# PowerSound9x_v002.net
KiCad netlist of a schematic drawn in EAGLE
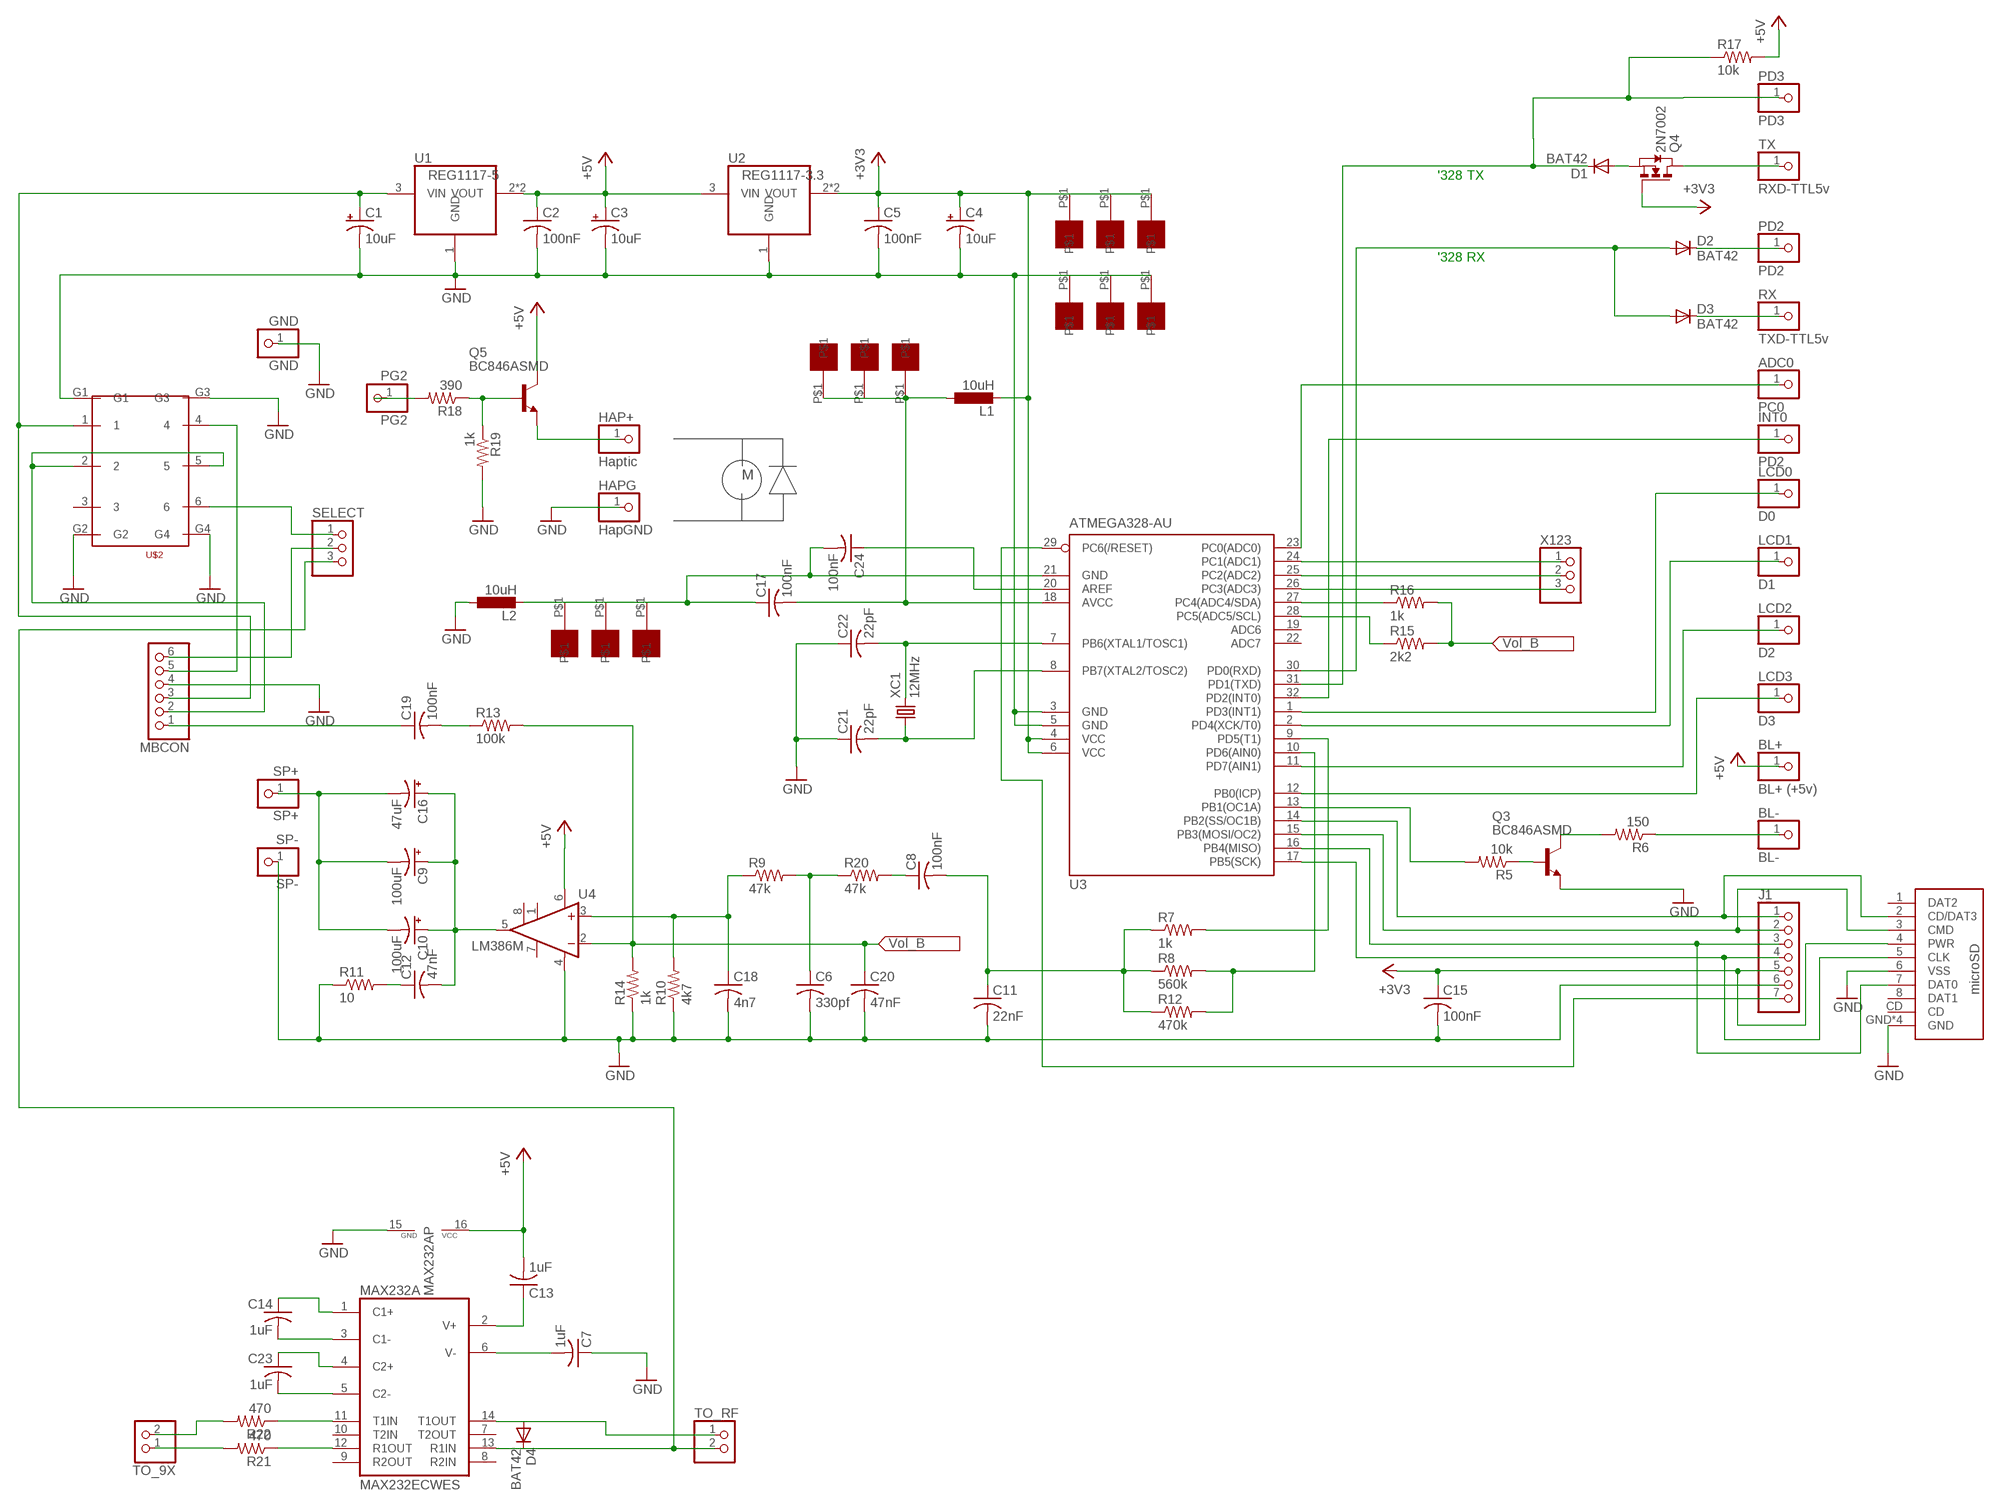
[diagram p0: schematic, sheet 1]

(export (version "E")
  (design (tool "Eeschema 10.0.6"))
  (components
    (comp (ref "ADC0")
      (value "PC0")
      (footprint "eagle-import:1X01")
      (libsource (lib "eagle-import") (part "PINHD-1X1"))
    )
    (comp (ref "BL+")
      (value "BL+ (+5v)")
      (footprint "eagle-import:1X01")
      (libsource (lib "eagle-import") (part "PINHD-1X1"))
    )
    (comp (ref "BL-")
      (value "BL-")
      (footprint "eagle-import:1X01")
      (libsource (lib "eagle-import") (part "PINHD-1X1"))
    )
    (comp (ref "C1")
      (value "10uF")
      (footprint "eagle-import:CT3528")
      (libsource (lib "eagle-import") (part "CPOL-USCT3528"))
    )
    (comp (ref "C2")
      (value "100nF")
      (footprint "eagle-import:C1206")
      (libsource (lib "eagle-import") (part "C-USC1206"))
    )
    (comp (ref "C3")
      (value "10uF")
      (footprint "eagle-import:CT3528")
      (libsource (lib "eagle-import") (part "CPOL-USCT3528"))
    )
    (comp (ref "C4")
      (value "10uF")
      (footprint "eagle-import:CT3528")
      (libsource (lib "eagle-import") (part "CPOL-USCT3528"))
    )
    (comp (ref "C5")
      (value "100nF")
      (footprint "eagle-import:C1206")
      (libsource (lib "eagle-import") (part "C-USC1206"))
    )
    (comp (ref "C6")
      (value "330pf")
      (footprint "eagle-import:C1206")
      (libsource (lib "eagle-import") (part "C-USC1206"))
    )
    (comp (ref "C7")
      (value "1uF")
      (footprint "eagle-import:C1206")
      (libsource (lib "eagle-import") (part "C-USC1206"))
    )
    (comp (ref "C8")
      (value "100nF")
      (footprint "eagle-import:C1206")
      (libsource (lib "eagle-import") (part "C-USC1206"))
    )
    (comp (ref "C9")
      (value "100uF")
      (footprint "eagle-import:CT6032")
      (libsource (lib "eagle-import") (part "CPOL-USCT6032"))
    )
    (comp (ref "C10")
      (value "100uF")
      (footprint "eagle-import:CT6032")
      (libsource (lib "eagle-import") (part "CPOL-USCT6032"))
    )
    (comp (ref "C11")
      (value "22nF")
      (footprint "eagle-import:C1206")
      (libsource (lib "eagle-import") (part "C-USC1206"))
    )
    (comp (ref "C12")
      (value "47nF")
      (footprint "eagle-import:C1206")
      (libsource (lib "eagle-import") (part "C-USC1206"))
    )
    (comp (ref "C13")
      (value "1uF")
      (footprint "eagle-import:C1206")
      (libsource (lib "eagle-import") (part "C-USC1206"))
    )
    (comp (ref "C14")
      (value "1uF")
      (footprint "eagle-import:C1206")
      (libsource (lib "eagle-import") (part "C-USC1206"))
    )
    (comp (ref "C15")
      (value "100nF")
      (footprint "eagle-import:C1206")
      (libsource (lib "eagle-import") (part "C-USC1206"))
    )
    (comp (ref "C16")
      (value "47uF")
      (footprint "eagle-import:CT6032")
      (libsource (lib "eagle-import") (part "CPOL-USCT6032"))
    )
    (comp (ref "C17")
      (value "100nF")
      (footprint "eagle-import:C1206")
      (libsource (lib "eagle-import") (part "C-USC1206"))
    )
    (comp (ref "C18")
      (value "4n7")
      (footprint "eagle-import:C1206")
      (libsource (lib "eagle-import") (part "C-USC1206"))
    )
    (comp (ref "C19")
      (value "100nF")
      (footprint "eagle-import:C1206")
      (libsource (lib "eagle-import") (part "C-USC1206"))
    )
    (comp (ref "C20")
      (value "47nF")
      (footprint "eagle-import:C1206")
      (libsource (lib "eagle-import") (part "C-USC1206"))
    )
    (comp (ref "C21")
      (value "22pF")
      (footprint "eagle-import:C1206")
      (libsource (lib "eagle-import") (part "C-USC1206"))
    )
    (comp (ref "C22")
      (value "22pF")
      (footprint "eagle-import:C1206")
      (libsource (lib "eagle-import") (part "C-USC1206"))
    )
    (comp (ref "C23")
      (value "1uF")
      (footprint "eagle-import:C1206")
      (libsource (lib "eagle-import") (part "C-USC1206"))
    )
    (comp (ref "C24")
      (value "100nF")
      (footprint "eagle-import:C1206")
      (libsource (lib "eagle-import") (part "C-USC1206"))
    )
    (comp (ref "D1")
      (value "BAT42")
      (footprint "eagle-import:SOD123")
      (libsource (lib "eagle-import") (part "DIODE-SOD123"))
    )
    (comp (ref "D2")
      (value "BAT42")
      (footprint "eagle-import:SOD123")
      (libsource (lib "eagle-import") (part "DIODE-SOD123"))
    )
    (comp (ref "D3")
      (value "BAT42")
      (footprint "eagle-import:SOD123")
      (libsource (lib "eagle-import") (part "DIODE-SOD123"))
    )
    (comp (ref "D4")
      (value "BAT42")
      (footprint "eagle-import:SOD123")
      (libsource (lib "eagle-import") (part "DIODE-SOD123"))
    )
    (comp (ref "GND")
      (value "GND")
      (footprint "eagle-import:1X01")
      (libsource (lib "eagle-import") (part "PINHD-1X1"))
    )
    (comp (ref "HAP+")
      (value "Haptic")
      (footprint "eagle-import:1X01")
      (libsource (lib "eagle-import") (part "PINHD-1X1"))
    )
    (comp (ref "HAPG")
      (value "HapGND")
      (footprint "eagle-import:1X01")
      (libsource (lib "eagle-import") (part "PINHD-1X1"))
    )
    (comp (ref "INT0")
      (value "PD2")
      (footprint "eagle-import:1X01")
      (libsource (lib "eagle-import") (part "PINHD-1X1"))
    )
    (comp (ref "J1")
      (value "PINHD-1X7")
      (footprint "eagle-import:1X07")
      (libsource (lib "eagle-import") (part "PINHD-1X7"))
    )
    (comp (ref "L1")
      (value "10uH")
      (footprint "eagle-import:L3225M")
      (libsource (lib "eagle-import") (part "L-EUL3225M"))
    )
    (comp (ref "L2")
      (value "10uH")
      (footprint "eagle-import:L3225M")
      (libsource (lib "eagle-import") (part "L-EUL3225M"))
    )
    (comp (ref "LCD0")
      (value "D0")
      (footprint "eagle-import:1X01")
      (libsource (lib "eagle-import") (part "PINHD-1X1"))
    )
    (comp (ref "LCD1")
      (value "D1")
      (footprint "eagle-import:1X01")
      (libsource (lib "eagle-import") (part "PINHD-1X1"))
    )
    (comp (ref "LCD2")
      (value "D2")
      (footprint "eagle-import:1X01")
      (libsource (lib "eagle-import") (part "PINHD-1X1"))
    )
    (comp (ref "LCD3")
      (value "D3")
      (footprint "eagle-import:1X01")
      (libsource (lib "eagle-import") (part "PINHD-1X1"))
    )
    (comp (ref "MAX232A")
      (value "MAX232ECWES")
      (footprint "eagle-import:SO16")
      (libsource (lib "eagle-import") (part "MAX232ECWES"))
    )
    (comp (ref "MBCON")
      (value "PINHD-1X6")
      (footprint "eagle-import:1X06")
      (libsource (lib "eagle-import") (part "PINHD-1X6"))
    )
    (comp (ref "PD2")
      (value "PD2")
      (footprint "eagle-import:1X01")
      (libsource (lib "eagle-import") (part "PINHD-1X1"))
    )
    (comp (ref "PD3")
      (value "PD3")
      (footprint "eagle-import:1X01")
      (libsource (lib "eagle-import") (part "PINHD-1X1"))
    )
    (comp (ref "PG2")
      (value "PG2")
      (footprint "eagle-import:1X01")
      (libsource (lib "eagle-import") (part "PINHD-1X1"))
    )
    (comp (ref "Q3")
      (value "BC846ASMD")
      (footprint "eagle-import:SOT23")
      (libsource (lib "eagle-import") (part "BC846SMDA"))
    )
    (comp (ref "Q4")
      (value "2N7002")
      (footprint "eagle-import:SOT-23")
      (libsource (lib "eagle-import") (part "NMOSSOT23"))
    )
    (comp (ref "Q5")
      (value "BC846ASMD")
      (footprint "eagle-import:SOT23")
      (libsource (lib "eagle-import") (part "BC846SMDA"))
    )
    (comp (ref "R5")
      (value "10k")
      (footprint "eagle-import:R1206")
      (libsource (lib "eagle-import") (part "R-US_R1206"))
    )
    (comp (ref "R6")
      (value "150")
      (footprint "eagle-import:R1206")
      (libsource (lib "eagle-import") (part "R-US_R1206"))
    )
    (comp (ref "R7")
      (value "1k")
      (footprint "eagle-import:R1206")
      (libsource (lib "eagle-import") (part "R-US_R1206"))
    )
    (comp (ref "R8")
      (value "560k")
      (footprint "eagle-import:R1206")
      (libsource (lib "eagle-import") (part "R-US_R1206"))
    )
    (comp (ref "R9")
      (value "47k")
      (footprint "eagle-import:R1206")
      (libsource (lib "eagle-import") (part "R-US_R1206"))
    )
    (comp (ref "R10")
      (value "4k7")
      (footprint "eagle-import:R1206")
      (libsource (lib "eagle-import") (part "R-US_R1206"))
    )
    (comp (ref "R11")
      (value "10")
      (footprint "eagle-import:R1206")
      (libsource (lib "eagle-import") (part "R-US_R1206"))
    )
    (comp (ref "R12")
      (value "470k")
      (footprint "eagle-import:R1206")
      (libsource (lib "eagle-import") (part "R-US_R1206"))
    )
    (comp (ref "R13")
      (value "100k")
      (footprint "eagle-import:R1206")
      (libsource (lib "eagle-import") (part "R-US_R1206"))
    )
    (comp (ref "R14")
      (value "1k")
      (footprint "eagle-import:R1206")
      (libsource (lib "eagle-import") (part "R-US_R1206"))
    )
    (comp (ref "R15")
      (value "2k2")
      (footprint "eagle-import:R1206")
      (libsource (lib "eagle-import") (part "R-US_R1206"))
    )
    (comp (ref "R16")
      (value "1k")
      (footprint "eagle-import:R1206")
      (libsource (lib "eagle-import") (part "R-US_R1206"))
    )
    (comp (ref "R17")
      (value "10k")
      (footprint "eagle-import:R1206")
      (libsource (lib "eagle-import") (part "R-US_R1206"))
    )
    (comp (ref "R18")
      (value "390")
      (footprint "eagle-import:R1206")
      (libsource (lib "eagle-import") (part "R-US_R1206"))
    )
    (comp (ref "R19")
      (value "1k")
      (footprint "eagle-import:R1206")
      (libsource (lib "eagle-import") (part "R-US_R1206"))
    )
    (comp (ref "R20")
      (value "47k")
      (footprint "eagle-import:R1206")
      (libsource (lib "eagle-import") (part "R-US_R1206"))
    )
    (comp (ref "R21")
      (value "470")
      (footprint "eagle-import:R1206")
      (libsource (lib "eagle-import") (part "R-US_R1206"))
    )
    (comp (ref "R22")
      (value "470")
      (footprint "eagle-import:R1206")
      (libsource (lib "eagle-import") (part "R-US_R1206"))
    )
    (comp (ref "RX")
      (value "TXD-TTL5v")
      (footprint "eagle-import:1X01")
      (libsource (lib "eagle-import") (part "PINHD-1X1"))
    )
    (comp (ref "SELECT")
      (value "PINHD-1X3")
      (footprint "eagle-import:1X03")
      (libsource (lib "eagle-import") (part "PINHD-1X3"))
    )
    (comp (ref "SP+")
      (value "SP+")
      (footprint "eagle-import:1X01")
      (libsource (lib "eagle-import") (part "PINHD-1X1"))
    )
    (comp (ref "SP-")
      (value "SP-")
      (footprint "eagle-import:1X01")
      (libsource (lib "eagle-import") (part "PINHD-1X1"))
    )
    (comp (ref "TO_9X")
      (value "PINHD-1X2")
      (footprint "eagle-import:1X02")
      (libsource (lib "eagle-import") (part "PINHD-1X2"))
    )
    (comp (ref "TO_RF")
      (value "PINHD-1X2")
      (footprint "eagle-import:1X02")
      (libsource (lib "eagle-import") (part "PINHD-1X2"))
    )
    (comp (ref "TX")
      (value "RXD-TTL5v")
      (footprint "eagle-import:1X01")
      (libsource (lib "eagle-import") (part "PINHD-1X1"))
    )
    (comp (ref "U$1")
      (value "PAD")
      (footprint "eagle-import:PAD")
      (libsource (lib "eagle-import") (part "PAD"))
    )
    (comp (ref "U$2")
      (value "SS22H02SS22H02")
      (footprint "eagle-import:SS22H02")
      (libsource (lib "eagle-import") (part "SS22H02SS22H02"))
    )
    (comp (ref "U$3")
      (value "112J-TDAR-R")
      (footprint "eagle-import:112J-TDAR-R")
      (libsource (lib "eagle-import") (part "112J-TDAR-R"))
    )
    (comp (ref "U$4")
      (value "PAD")
      (footprint "eagle-import:PAD")
      (libsource (lib "eagle-import") (part "PAD"))
    )
    (comp (ref "U$5")
      (value "PAD")
      (footprint "eagle-import:PAD")
      (libsource (lib "eagle-import") (part "PAD"))
    )
    (comp (ref "U$6")
      (value "PAD")
      (footprint "eagle-import:PAD")
      (libsource (lib "eagle-import") (part "PAD"))
    )
    (comp (ref "U$7")
      (value "PAD")
      (footprint "eagle-import:PAD")
      (libsource (lib "eagle-import") (part "PAD"))
    )
    (comp (ref "U$8")
      (value "PAD")
      (footprint "eagle-import:PAD")
      (libsource (lib "eagle-import") (part "PAD"))
    )
    (comp (ref "U$9")
      (value "PAD")
      (footprint "eagle-import:PAD")
      (libsource (lib "eagle-import") (part "PAD"))
    )
    (comp (ref "U$10")
      (value "PAD")
      (footprint "eagle-import:PAD")
      (libsource (lib "eagle-import") (part "PAD"))
    )
    (comp (ref "U$11")
      (value "PAD")
      (footprint "eagle-import:PAD")
      (libsource (lib "eagle-import") (part "PAD"))
    )
    (comp (ref "U$12")
      (value "PAD")
      (footprint "eagle-import:PAD")
      (libsource (lib "eagle-import") (part "PAD"))
    )
    (comp (ref "U$13")
      (value "PAD")
      (footprint "eagle-import:PAD")
      (libsource (lib "eagle-import") (part "PAD"))
    )
    (comp (ref "U$14")
      (value "PAD")
      (footprint "eagle-import:PAD")
      (libsource (lib "eagle-import") (part "PAD"))
    )
    (comp (ref "U1")
      (value "REG1117-5")
      (footprint "eagle-import:SOT223")
      (fields (field (name "MPN") "REG1117"))
      (libsource (lib "eagle-import") (part "REG1117"))
    )
    (comp (ref "U2")
      (value "REG1117-3.3")
      (footprint "eagle-import:SOT223")
      (fields (field (name "MPN") "REG1117"))
      (libsource (lib "eagle-import") (part "REG1117"))
    )
    (comp (ref "U3")
      (value "ATMEGA328-AU")
      (footprint "eagle-import:TQFP32-08")
      (fields (field (name "MPN") "ATMEGA8-16AU"))
      (libsource (lib "eagle-import") (part "MEGA8-AI"))
    )
    (comp (ref "U4")
      (value "LM386M")
      (footprint "eagle-import:SO08")
      (libsource (lib "eagle-import") (part "LM386?-M1"))
    )
    (comp (ref "X123")
      (value "PINHD-1X3")
      (footprint "eagle-import:1X03")
      (libsource (lib "eagle-import") (part "PINHD-1X3"))
    )
    (comp (ref "XC1")
      (value "12MHz")
      (footprint "eagle-import:HC49UP")
      (libsource (lib "eagle-import") (part "CRYSTALHC49UP"))
    )
  )
  (nets
    (net (code "1") (name "+3V3") (class "Default")
      (node (ref "C15") (pin "1") (pinfunction "1_1") (pintype "passive"))
      (node (ref "C4") (pin "+") (pinfunction "+_+") (pintype "passive"))
      (node (ref "C5") (pin "1") (pinfunction "1_1") (pintype "passive"))
      (node (ref "J1") (pin "5") (pinfunction "5_5") (pintype "passive"))
      (node (ref "L1") (pin "2") (pinfunction "2_2") (pintype "passive"))
      (node (ref "Q4") (pin "3") (pinfunction "G_3") (pintype "passive"))
      (node (ref "U$10") (pin "P$1") (pinfunction "P$1_P$1") (pintype "bidirectional"))
      (node (ref "U$11") (pin "P$1") (pinfunction "P$1_P$1") (pintype "bidirectional"))
      (node (ref "U$3") (pin "4") (pinfunction "PWR_4") (pintype "bidirectional"))
      (node (ref "U$9") (pin "P$1") (pinfunction "P$1_P$1") (pintype "bidirectional"))
      (node (ref "U2") (pin "2") (pinfunction "VOUT_2") (pintype "output"))
      (node (ref "U2") (pin "4") (pinfunction "VOUT_4") (pintype "output"))
      (node (ref "U3") (pin "4") (pinfunction "VCC_4") (pintype "power_in"))
      (node (ref "U3") (pin "6") (pinfunction "VCC_6") (pintype "power_in"))
    )
    (net (code "2") (name "+5V") (class "Default")
      (node (ref "BL+") (pin "1") (pinfunction "1_1") (pintype "passive"))
      (node (ref "C13") (pin "2") (pinfunction "2_2") (pintype "passive"))
      (node (ref "C2") (pin "1") (pinfunction "1_1") (pintype "passive"))
      (node (ref "C3") (pin "+") (pinfunction "+_+") (pintype "passive"))
      (node (ref "MAX232A") (pin "16") (pinfunction "VCC_16") (pintype "power_in"))
      (node (ref "Q5") (pin "3") (pinfunction "C_3") (pintype "passive"))
      (node (ref "R17") (pin "2") (pinfunction "2_2") (pintype "passive"))
      (node (ref "U1") (pin "2") (pinfunction "VOUT_2") (pintype "output"))
      (node (ref "U1") (pin "4") (pinfunction "VOUT_4") (pintype "output"))
      (node (ref "U2") (pin "3") (pinfunction "VIN_3") (pintype "input"))
      (node (ref "U4") (pin "6") (pinfunction "VS_6") (pintype "power_in"))
    )
    (net (code "3") (name "/VOL_B") (class "Default")
      (node (ref "C20") (pin "1") (pinfunction "1_1") (pintype "passive"))
      (node (ref "R13") (pin "2") (pinfunction "2_2") (pintype "passive"))
      (node (ref "R14") (pin "2") (pinfunction "2_2") (pintype "passive"))
      (node (ref "R15") (pin "2") (pinfunction "2_2") (pintype "passive"))
      (node (ref "R16") (pin "2") (pinfunction "2_2") (pintype "passive"))
      (node (ref "U4") (pin "2") (pinfunction "-IN_2") (pintype "input"))
    )
    (net (code "4") (name "GND") (class "Default")
      (node (ref "C1") (pin "-") (pinfunction "-_-") (pintype "passive"))
      (node (ref "C11") (pin "2") (pinfunction "2_2") (pintype "passive"))
      (node (ref "C15") (pin "2") (pinfunction "2_2") (pintype "passive"))
      (node (ref "C18") (pin "2") (pinfunction "2_2") (pintype "passive"))
      (node (ref "C2") (pin "2") (pinfunction "2_2") (pintype "passive"))
      (node (ref "C20") (pin "2") (pinfunction "2_2") (pintype "passive"))
      (node (ref "C21") (pin "1") (pinfunction "1_1") (pintype "passive"))
      (node (ref "C22") (pin "1") (pinfunction "1_1") (pintype "passive"))
      (node (ref "C3") (pin "-") (pinfunction "-_-") (pintype "passive"))
      (node (ref "C4") (pin "-") (pinfunction "-_-") (pintype "passive"))
      (node (ref "C5") (pin "2") (pinfunction "2_2") (pintype "passive"))
      (node (ref "C6") (pin "2") (pinfunction "2_2") (pintype "passive"))
      (node (ref "C7") (pin "1") (pinfunction "1_1") (pintype "passive"))
      (node (ref "GND") (pin "1") (pinfunction "1_1") (pintype "passive"))
      (node (ref "HAPG") (pin "1") (pinfunction "1_1") (pintype "passive"))
      (node (ref "J1") (pin "6") (pinfunction "6_6") (pintype "passive"))
      (node (ref "L2") (pin "1") (pinfunction "1_1") (pintype "passive"))
      (node (ref "MAX232A") (pin "15") (pinfunction "GND_15") (pintype "power_in"))
      (node (ref "MBCON") (pin "4") (pinfunction "4_4") (pintype "passive"))
      (node (ref "Q3") (pin "2") (pinfunction "E_2") (pintype "passive"))
      (node (ref "R10") (pin "1") (pinfunction "1_1") (pintype "passive"))
      (node (ref "R11") (pin "1") (pinfunction "1_1") (pintype "passive"))
      (node (ref "R14") (pin "1") (pinfunction "1_1") (pintype "passive"))
      (node (ref "R19") (pin "2") (pinfunction "2_2") (pintype "passive"))
      (node (ref "SP-") (pin "1") (pinfunction "1_1") (pintype "passive"))
      (node (ref "U$12") (pin "P$1") (pinfunction "P$1_P$1") (pintype "bidirectional"))
      (node (ref "U$13") (pin "P$1") (pinfunction "P$1_P$1") (pintype "bidirectional"))
      (node (ref "U$14") (pin "P$1") (pinfunction "P$1_P$1") (pintype "bidirectional"))
      (node (ref "U$2") (pin "G1") (pinfunction "G1_G1") (pintype "bidirectional"))
      (node (ref "U$2") (pin "G2") (pinfunction "G2_G2") (pintype "bidirectional"))
      (node (ref "U$2") (pin "G3") (pinfunction "G3_G3") (pintype "bidirectional"))
      (node (ref "U$2") (pin "G4") (pinfunction "G4_G4") (pintype "bidirectional"))
      (node (ref "U$3") (pin "6") (pinfunction "VSS_6") (pintype "bidirectional"))
      (node (ref "U$3") (pin "GND") (pinfunction "GND_GND") (pintype "bidirectional"))
      (node (ref "U$3") (pin "GND1") (pinfunction "GND_GND1") (pintype "bidirectional"))
      (node (ref "U$3") (pin "GND2") (pinfunction "GND_GND2") (pintype "bidirectional"))
      (node (ref "U$3") (pin "GND3") (pinfunction "GND_GND3") (pintype "bidirectional"))
      (node (ref "U1") (pin "1") (pinfunction "GND_1") (pintype "power_in"))
      (node (ref "U2") (pin "1") (pinfunction "GND_1") (pintype "power_in"))
      (node (ref "U3") (pin "3") (pinfunction "GND_3") (pintype "power_in"))
      (node (ref "U3") (pin "5") (pinfunction "GND_5") (pintype "power_in"))
      (node (ref "U4") (pin "4") (pinfunction "GND_4") (pintype "power_in"))
    )
    (net (code "5") (name "Net-(BL--Pad1)") (class "Default")
      (node (ref "BL-") (pin "1") (pinfunction "1_1") (pintype "passive"))
      (node (ref "R6") (pin "1") (pinfunction "1_1") (pintype "passive"))
    )
    (net (code "6") (name "Net-(C6-Pad1)") (class "Default")
      (node (ref "C6") (pin "1") (pinfunction "1_1") (pintype "passive"))
      (node (ref "R20") (pin "1") (pinfunction "1_1") (pintype "passive"))
      (node (ref "R9") (pin "2") (pinfunction "2_2") (pintype "passive"))
    )
    (net (code "7") (name "Net-(C8-Pad1)") (class "Default")
      (node (ref "C8") (pin "1") (pinfunction "1_1") (pintype "passive"))
      (node (ref "R20") (pin "2") (pinfunction "2_2") (pintype "passive"))
    )
    (net (code "8") (name "Net-(C10-Pad-)") (class "Default")
      (node (ref "C10") (pin "-") (pinfunction "-_-") (pintype "passive"))
      (node (ref "C16") (pin "-") (pinfunction "-_-") (pintype "passive"))
      (node (ref "C9") (pin "-") (pinfunction "-_-") (pintype "passive"))
      (node (ref "SP+") (pin "1") (pinfunction "1_1") (pintype "passive"))
    )
    (net (code "9") (name "Net-(C11-Pad1)") (class "Default")
      (node (ref "C11") (pin "1") (pinfunction "1_1") (pintype "passive"))
      (node (ref "C8") (pin "2") (pinfunction "2_2") (pintype "passive"))
      (node (ref "R12") (pin "1") (pinfunction "1_1") (pintype "passive"))
      (node (ref "R7") (pin "1") (pinfunction "1_1") (pintype "passive"))
      (node (ref "R8") (pin "1") (pinfunction "1_1") (pintype "passive"))
    )
    (net (code "10") (name "Net-(C12-Pad1)") (class "Default")
      (node (ref "C12") (pin "1") (pinfunction "1_1") (pintype "passive"))
      (node (ref "R11") (pin "2") (pinfunction "2_2") (pintype "passive"))
    )
    (net (code "11") (name "Net-(C17-Pad1)") (class "Default")
      (node (ref "C17") (pin "1") (pinfunction "1_1") (pintype "passive"))
      (node (ref "C24") (pin "2") (pinfunction "2_2") (pintype "passive"))
      (node (ref "L2") (pin "2") (pinfunction "2_2") (pintype "passive"))
      (node (ref "U$6") (pin "P$1") (pinfunction "P$1_P$1") (pintype "bidirectional"))
      (node (ref "U$7") (pin "P$1") (pinfunction "P$1_P$1") (pintype "bidirectional"))
      (node (ref "U$8") (pin "P$1") (pinfunction "P$1_P$1") (pintype "bidirectional"))
      (node (ref "U3") (pin "21") (pinfunction "GND_21") (pintype "power_in"))
    )
    (net (code "12") (name "Net-(C19-Pad1)") (class "Default")
      (node (ref "C19") (pin "1") (pinfunction "1_1") (pintype "passive"))
      (node (ref "MBCON") (pin "1") (pinfunction "1_1") (pintype "passive"))
    )
    (net (code "13") (name "Net-(C19-Pad2)") (class "Default")
      (node (ref "C19") (pin "2") (pinfunction "2_2") (pintype "passive"))
      (node (ref "R13") (pin "1") (pinfunction "1_1") (pintype "passive"))
    )
    (net (code "14") (name "Net-(D2-PadC)") (class "Default")
      (node (ref "D2") (pin "C") (pinfunction "C_C") (pintype "passive"))
      (node (ref "PD2") (pin "1") (pinfunction "1_1") (pintype "passive"))
    )
    (net (code "15") (name "Net-(D3-PadC)") (class "Default")
      (node (ref "D3") (pin "C") (pinfunction "C_C") (pintype "passive"))
      (node (ref "RX") (pin "1") (pinfunction "1_1") (pintype "passive"))
    )
    (net (code "16") (name "Net-(MAX232AA-C1+)") (class "Default")
      (node (ref "C14") (pin "1") (pinfunction "1_1") (pintype "passive"))
      (node (ref "MAX232A") (pin "1") (pinfunction "C1+_1") (pintype "bidirectional"))
    )
    (net (code "17") (name "Net-(MAX232AA-C1-)") (class "Default")
      (node (ref "C14") (pin "2") (pinfunction "2_2") (pintype "passive"))
      (node (ref "MAX232A") (pin "3") (pinfunction "C1-_3") (pintype "bidirectional"))
    )
    (net (code "18") (name "Net-(MAX232AA-C2+)") (class "Default")
      (node (ref "C23") (pin "1") (pinfunction "1_1") (pintype "passive"))
      (node (ref "MAX232A") (pin "4") (pinfunction "C2+_4") (pintype "bidirectional"))
    )
    (net (code "19") (name "Net-(MAX232AA-C2-)") (class "Default")
      (node (ref "C23") (pin "2") (pinfunction "2_2") (pintype "passive"))
      (node (ref "MAX232A") (pin "5") (pinfunction "C2-_5") (pintype "bidirectional"))
    )
    (net (code "20") (name "Net-(MAX232AA-R1IN)") (class "Default")
      (node (ref "D4") (pin "C") (pinfunction "C_C") (pintype "passive"))
      (node (ref "MAX232A") (pin "13") (pinfunction "R1IN_13") (pintype "input"))
      (node (ref "SELECT") (pin "3") (pinfunction "3_3") (pintype "passive"))
      (node (ref "TO_RF") (pin "2") (pinfunction "2_2") (pintype "passive"))
    )
    (net (code "21") (name "Net-(MAX232AA-R1OUT)") (class "Default")
      (node (ref "MAX232A") (pin "12") (pinfunction "R1OUT_12") (pintype "output"))
      (node (ref "R21") (pin "1") (pinfunction "1_1") (pintype "passive"))
    )
    (net (code "22") (name "Net-(MAX232AA-T1IN)") (class "Default")
      (node (ref "MAX232A") (pin "11") (pinfunction "T1IN_11") (pintype "input"))
      (node (ref "R22") (pin "1") (pinfunction "1_1") (pintype "passive"))
    )
    (net (code "23") (name "Net-(MAX232AA-T1OUT)") (class "Default")
      (node (ref "D4") (pin "A") (pinfunction "A_A") (pintype "passive"))
      (node (ref "MAX232A") (pin "14") (pinfunction "T1OUT_14") (pintype "output"))
      (node (ref "TO_RF") (pin "1") (pinfunction "1_1") (pintype "passive"))
    )
    (net (code "24") (name "Net-(MAX232AA-V+)") (class "Default")
      (node (ref "C13") (pin "1") (pinfunction "1_1") (pintype "passive"))
      (node (ref "MAX232A") (pin "2") (pinfunction "V+_2") (pintype "bidirectional"))
    )
    (net (code "25") (name "Net-(MAX232AA-V-)") (class "Default")
      (node (ref "C7") (pin "2") (pinfunction "2_2") (pintype "passive"))
      (node (ref "MAX232A") (pin "6") (pinfunction "V-_6") (pintype "bidirectional"))
    )
    (net (code "26") (name "Net-(MBCON-Pad2)") (class "Default")
      (node (ref "MBCON") (pin "2") (pinfunction "2_2") (pintype "passive"))
      (node (ref "U$2") (pin "2") (pinfunction "2_2") (pintype "bidirectional"))
      (node (ref "U$2") (pin "5") (pinfunction "5_5") (pintype "bidirectional"))
    )
    (net (code "27") (name "Net-(MBCON-Pad5)") (class "Default")
      (node (ref "MBCON") (pin "5") (pinfunction "5_5") (pintype "passive"))
      (node (ref "U$2") (pin "4") (pinfunction "4_4") (pintype "bidirectional"))
    )
    (net (code "28") (name "Net-(MBCON-Pad6)") (class "Default")
      (node (ref "MBCON") (pin "6") (pinfunction "6_6") (pintype "passive"))
      (node (ref "SELECT") (pin "2") (pinfunction "2_2") (pintype "passive"))
    )
    (net (code "29") (name "Net-(PG2-Pad1)") (class "Default")
      (node (ref "PG2") (pin "1") (pinfunction "1_1") (pintype "passive"))
      (node (ref "R18") (pin "2") (pinfunction "2_2") (pintype "passive"))
    )
    (net (code "30") (name "Net-(Q3-B)") (class "Default")
      (node (ref "Q3") (pin "1") (pinfunction "B_1") (pintype "passive"))
      (node (ref "R5") (pin "1") (pinfunction "1_1") (pintype "passive"))
    )
    (net (code "31") (name "Net-(Q3-C)") (class "Default")
      (node (ref "Q3") (pin "3") (pinfunction "C_3") (pintype "passive"))
      (node (ref "R6") (pin "2") (pinfunction "2_2") (pintype "passive"))
    )
    (net (code "32") (name "Net-(Q4-D)") (class "Default")
      (node (ref "Q4") (pin "1") (pinfunction "D_1") (pintype "passive"))
      (node (ref "TX") (pin "1") (pinfunction "1_1") (pintype "passive"))
    )
    (net (code "33") (name "Net-(Q4-S)") (class "Default")
      (node (ref "D1") (pin "A") (pinfunction "A_A") (pintype "passive"))
      (node (ref "Q4") (pin "2") (pinfunction "S_2") (pintype "passive"))
    )
    (net (code "34") (name "Net-(Q5-B)") (class "Default")
      (node (ref "Q5") (pin "1") (pinfunction "B_1") (pintype "passive"))
      (node (ref "R18") (pin "1") (pinfunction "1_1") (pintype "passive"))
      (node (ref "R19") (pin "1") (pinfunction "1_1") (pintype "passive"))
    )
    (net (code "35") (name "Net-(Q5-E)") (class "Default")
      (node (ref "HAP+") (pin "1") (pinfunction "1_1") (pintype "passive"))
      (node (ref "Q5") (pin "2") (pinfunction "E_2") (pintype "passive"))
    )
    (net (code "36") (name "Net-(R21-Pad2)") (class "Default")
      (node (ref "R21") (pin "2") (pinfunction "2_2") (pintype "passive"))
      (node (ref "TO_9X") (pin "1") (pinfunction "1_1") (pintype "passive"))
    )
    (net (code "37") (name "Net-(R22-Pad2)") (class "Default")
      (node (ref "R22") (pin "2") (pinfunction "2_2") (pintype "passive"))
      (node (ref "TO_9X") (pin "2") (pinfunction "2_2") (pintype "passive"))
    )
    (net (code "38") (name "Net-(SELECT-Pad1)") (class "Default")
      (node (ref "SELECT") (pin "1") (pinfunction "1_1") (pintype "passive"))
      (node (ref "U$2") (pin "6") (pinfunction "6_6") (pintype "bidirectional"))
    )
    (net (code "39") (name "Net-(U$3-CD{slash}DAT3)") (class "Default")
      (node (ref "J1") (pin "1") (pinfunction "1_1") (pintype "passive"))
      (node (ref "U$3") (pin "2") (pinfunction "CD/DAT3_2") (pintype "bidirectional"))
      (node (ref "U3") (pin "14") (pinfunction "PB2(SS/OC1B)_14") (pintype "bidirectional"))
    )
    (net (code "40") (name "Net-(U$3-CLK)") (class "Default")
      (node (ref "J1") (pin "4") (pinfunction "4_4") (pintype "passive"))
      (node (ref "U$3") (pin "5") (pinfunction "CLK_5") (pintype "bidirectional"))
      (node (ref "U3") (pin "17") (pinfunction "PB5(SCK)_17") (pintype "bidirectional"))
    )
    (net (code "41") (name "Net-(U$3-CMD)") (class "Default")
      (node (ref "J1") (pin "2") (pinfunction "2_2") (pintype "passive"))
      (node (ref "U$3") (pin "3") (pinfunction "CMD_3") (pintype "bidirectional"))
      (node (ref "U3") (pin "15") (pinfunction "PB3(MOSI/OC2)_15") (pintype "bidirectional"))
    )
    (net (code "42") (name "Net-(U$3-DAT0)") (class "Default")
      (node (ref "J1") (pin "3") (pinfunction "3_3") (pintype "passive"))
      (node (ref "U$3") (pin "7") (pinfunction "DAT0_7") (pintype "bidirectional"))
      (node (ref "U3") (pin "16") (pinfunction "PB4(MISO)_16") (pintype "bidirectional"))
    )
    (net (code "43") (name "Net-(U1-VIN)") (class "Default")
      (node (ref "C1") (pin "+") (pinfunction "+_+") (pintype "passive"))
      (node (ref "MBCON") (pin "3") (pinfunction "3_3") (pintype "passive"))
      (node (ref "U$2") (pin "1") (pinfunction "1_1") (pintype "bidirectional"))
      (node (ref "U1") (pin "3") (pinfunction "VIN_3") (pintype "input"))
    )
    (net (code "44") (name "Net-(U3-AREF)") (class "Default")
      (node (ref "C24") (pin "1") (pinfunction "1_1") (pintype "passive"))
      (node (ref "U3") (pin "20") (pinfunction "AREF_20") (pintype "passive"))
    )
    (net (code "45") (name "Net-(U3-AVCC)") (class "Default")
      (node (ref "C17") (pin "2") (pinfunction "2_2") (pintype "passive"))
      (node (ref "L1") (pin "1") (pinfunction "1_1") (pintype "passive"))
      (node (ref "U$1") (pin "P$1") (pinfunction "P$1_P$1") (pintype "bidirectional"))
      (node (ref "U$4") (pin "P$1") (pinfunction "P$1_P$1") (pintype "bidirectional"))
      (node (ref "U$5") (pin "P$1") (pinfunction "P$1_P$1") (pintype "bidirectional"))
      (node (ref "U3") (pin "18") (pinfunction "AVCC_18") (pintype "power_in"))
    )
    (net (code "46") (name "Net-(U3-PB0(ICP))") (class "Default")
      (node (ref "LCD3") (pin "1") (pinfunction "1_1") (pintype "passive"))
      (node (ref "U3") (pin "12") (pinfunction "PB0(ICP)_12") (pintype "bidirectional"))
    )
    (net (code "47") (name "Net-(U3-PB1(OC1A))") (class "Default")
      (node (ref "R5") (pin "2") (pinfunction "2_2") (pintype "passive"))
      (node (ref "U3") (pin "13") (pinfunction "PB1(OC1A)_13") (pintype "bidirectional"))
    )
    (net (code "48") (name "Net-(U3-PB6(XTAL1{slash}TOSC1))") (class "Default")
      (node (ref "C22") (pin "2") (pinfunction "2_2") (pintype "passive"))
      (node (ref "U3") (pin "7") (pinfunction "PB6(XTAL1/TOSC1)_7") (pintype "bidirectional"))
      (node (ref "XC1") (pin "2") (pinfunction "2_2") (pintype "passive"))
    )
    (net (code "49") (name "Net-(U3-PB7(XTAL2{slash}TOSC2))") (class "Default")
      (node (ref "C21") (pin "2") (pinfunction "2_2") (pintype "passive"))
      (node (ref "U3") (pin "8") (pinfunction "PB7(XTAL2/TOSC2)_8") (pintype "bidirectional"))
      (node (ref "XC1") (pin "1") (pinfunction "1_1") (pintype "passive"))
    )
    (net (code "50") (name "Net-(U3-PC0(ADC0))") (class "Default")
      (node (ref "ADC0") (pin "1") (pinfunction "1_1") (pintype "passive"))
      (node (ref "U3") (pin "23") (pinfunction "PC0(ADC0)_23") (pintype "bidirectional"))
    )
    (net (code "51") (name "Net-(U3-PC1(ADC1))") (class "Default")
      (node (ref "U3") (pin "24") (pinfunction "PC1(ADC1)_24") (pintype "bidirectional"))
      (node (ref "X123") (pin "1") (pinfunction "1_1") (pintype "passive"))
    )
    (net (code "52") (name "Net-(U3-PC2(ADC2))") (class "Default")
      (node (ref "U3") (pin "25") (pinfunction "PC2(ADC2)_25") (pintype "bidirectional"))
      (node (ref "X123") (pin "2") (pinfunction "2_2") (pintype "passive"))
    )
    (net (code "53") (name "Net-(U3-PC3(ADC3))") (class "Default")
      (node (ref "U3") (pin "26") (pinfunction "PC3(ADC3)_26") (pintype "bidirectional"))
      (node (ref "X123") (pin "3") (pinfunction "3_3") (pintype "passive"))
    )
    (net (code "54") (name "Net-(U3-PC4(ADC4{slash}SDA))") (class "Default")
      (node (ref "R16") (pin "1") (pinfunction "1_1") (pintype "passive"))
      (node (ref "U3") (pin "27") (pinfunction "PC4(ADC4/SDA)_27") (pintype "bidirectional"))
    )
    (net (code "55") (name "Net-(U3-PC5(ADC5{slash}SCL))") (class "Default")
      (node (ref "R15") (pin "1") (pinfunction "1_1") (pintype "passive"))
      (node (ref "U3") (pin "28") (pinfunction "PC5(ADC5/SCL)_28") (pintype "bidirectional"))
    )
    (net (code "56") (name "Net-(U3-PC6({slash}RESET))") (class "Default")
      (node (ref "J1") (pin "7") (pinfunction "7_7") (pintype "passive"))
      (node (ref "U3") (pin "29") (pinfunction "PC6(/RESET)_29") (pintype "bidirectional"))
    )
    (net (code "57") (name "Net-(U3-PD0(RXD))") (class "Default")
      (node (ref "D2") (pin "A") (pinfunction "A_A") (pintype "passive"))
      (node (ref "D3") (pin "A") (pinfunction "A_A") (pintype "passive"))
      (node (ref "U3") (pin "30") (pinfunction "PD0(RXD)_30") (pintype "bidirectional"))
    )
    (net (code "58") (name "Net-(U3-PD1(TXD))") (class "Default")
      (node (ref "D1") (pin "C") (pinfunction "C_C") (pintype "passive"))
      (node (ref "PD3") (pin "1") (pinfunction "1_1") (pintype "passive"))
      (node (ref "R17") (pin "1") (pinfunction "1_1") (pintype "passive"))
      (node (ref "U3") (pin "31") (pinfunction "PD1(TXD)_31") (pintype "bidirectional"))
    )
    (net (code "59") (name "Net-(U3-PD2(INT0))") (class "Default")
      (node (ref "INT0") (pin "1") (pinfunction "1_1") (pintype "passive"))
      (node (ref "U3") (pin "32") (pinfunction "PD2(INT0)_32") (pintype "bidirectional"))
    )
    (net (code "60") (name "Net-(U3-PD3(INT1))") (class "Default")
      (node (ref "LCD0") (pin "1") (pinfunction "1_1") (pintype "passive"))
      (node (ref "U3") (pin "1") (pinfunction "PD3(INT1)_1") (pintype "bidirectional"))
    )
    (net (code "61") (name "Net-(U3-PD4(XCK{slash}T0))") (class "Default")
      (node (ref "LCD1") (pin "1") (pinfunction "1_1") (pintype "passive"))
      (node (ref "U3") (pin "2") (pinfunction "PD4(XCK/T0)_2") (pintype "bidirectional"))
    )
    (net (code "62") (name "Net-(U3-PD5(T1))") (class "Default")
      (node (ref "R7") (pin "2") (pinfunction "2_2") (pintype "passive"))
      (node (ref "U3") (pin "9") (pinfunction "PD5(T1)_9") (pintype "bidirectional"))
    )
    (net (code "63") (name "Net-(U3-PD6(AIN0))") (class "Default")
      (node (ref "R12") (pin "2") (pinfunction "2_2") (pintype "passive"))
      (node (ref "R8") (pin "2") (pinfunction "2_2") (pintype "passive"))
      (node (ref "U3") (pin "10") (pinfunction "PD6(AIN0)_10") (pintype "bidirectional"))
    )
    (net (code "64") (name "Net-(U3-PD7(AIN1))") (class "Default")
      (node (ref "LCD2") (pin "1") (pinfunction "1_1") (pintype "passive"))
      (node (ref "U3") (pin "11") (pinfunction "PD7(AIN1)_11") (pintype "bidirectional"))
    )
    (net (code "65") (name "Net-(U4-+IN)") (class "Default")
      (node (ref "C18") (pin "1") (pinfunction "1_1") (pintype "passive"))
      (node (ref "R10") (pin "2") (pinfunction "2_2") (pintype "passive"))
      (node (ref "R9") (pin "1") (pinfunction "1_1") (pintype "passive"))
      (node (ref "U4") (pin "3") (pinfunction "+IN_3") (pintype "input"))
    )
    (net (code "66") (name "Net-(U4-OUT)") (class "Default")
      (node (ref "C10") (pin "+") (pinfunction "+_+") (pintype "passive"))
      (node (ref "C12") (pin "2") (pinfunction "2_2") (pintype "passive"))
      (node (ref "C16") (pin "+") (pinfunction "+_+") (pintype "passive"))
      (node (ref "C9") (pin "+") (pinfunction "+_+") (pintype "passive"))
      (node (ref "U4") (pin "5") (pinfunction "OUT_5") (pintype "output"))
    )
    (net (code "67") (name "unconnected-(MAX232AA-R2IN-Pad8)") (class "Default")
      (node (ref "MAX232A") (pin "8") (pinfunction "R2IN_8") (pintype "input"))
    )
    (net (code "68") (name "unconnected-(MAX232AA-R2OUT-Pad9)") (class "Default")
      (node (ref "MAX232A") (pin "9") (pinfunction "R2OUT_9") (pintype "output"))
    )
    (net (code "69") (name "unconnected-(MAX232AA-T2IN-Pad10)") (class "Default")
      (node (ref "MAX232A") (pin "10") (pinfunction "T2IN_10") (pintype "input"))
    )
    (net (code "70") (name "unconnected-(MAX232AA-T2OUT-Pad7)") (class "Default")
      (node (ref "MAX232A") (pin "7") (pinfunction "T2OUT_7") (pintype "output"))
    )
    (net (code "71") (name "unconnected-(U$2-Pad3)") (class "Default")
      (node (ref "U$2") (pin "3") (pinfunction "3_3") (pintype "bidirectional"))
    )
    (net (code "72") (name "unconnected-(U$3-DAT1-Pad8)") (class "Default")
      (node (ref "U$3") (pin "8") (pinfunction "DAT1_8") (pintype "bidirectional"))
    )
    (net (code "73") (name "unconnected-(U$3-DAT2-Pad1)") (class "Default")
      (node (ref "U$3") (pin "1") (pinfunction "DAT2_1") (pintype "bidirectional"))
    )
    (net (code "74") (name "unconnected-(U$3-PadCD)") (class "Default")
      (node (ref "U$3") (pin "CD") (pinfunction "CD_CD") (pintype "bidirectional"))
    )
    (net (code "75") (name "unconnected-(U3-ADC6-Pad19)") (class "Default")
      (node (ref "U3") (pin "19") (pinfunction "ADC6_19") (pintype "bidirectional"))
    )
    (net (code "76") (name "unconnected-(U3-ADC7-Pad22)") (class "Default")
      (node (ref "U3") (pin "22") (pinfunction "ADC7_22") (pintype "bidirectional"))
    )
    (net (code "77") (name "unconnected-(U4-BYPASS-Pad7)") (class "Default")
      (node (ref "U4") (pin "7") (pinfunction "BYPASS_7") (pintype "passive"))
    )
    (net (code "78") (name "unconnected-(U4-GAIN-Pad1)") (class "Default")
      (node (ref "U4") (pin "1") (pinfunction "GAIN_1") (pintype "passive"))
    )
    (net (code "79") (name "unconnected-(U4-GAIN-Pad8)") (class "Default")
      (node (ref "U4") (pin "8") (pinfunction "GAIN_8") (pintype "passive"))
    )
  )
)
